# power_cpu.net
KiCad netlist of a schematic drawn in Altium Designer
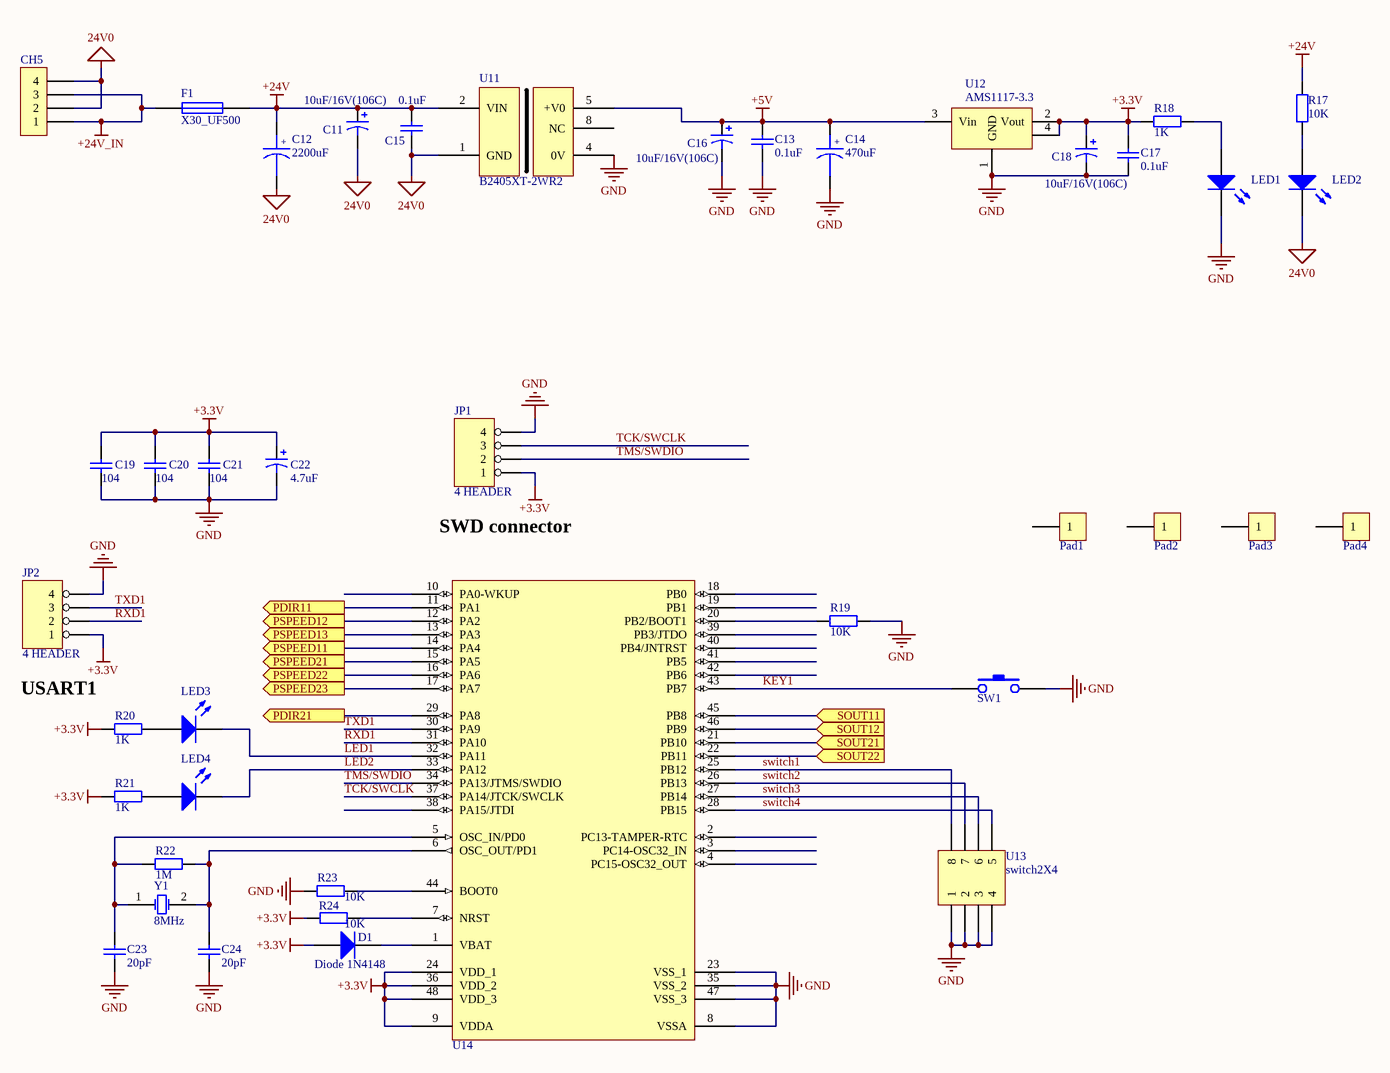
[diagram p0: power_cpu.SchDoc]

(export (version "E")
  (design (tool "Eeschema 10.0.6"))
  (components
    (comp (ref "C11")
      (value "10uF/16V(106C)")
      (footprint "CAP A-3216")
      (description "Polarized Capacitor (Surface Mount)")
      (fields (field (name "Comment") "Cap Pol3") (field (name "PUBLISHER") "Altium Limited"))
      (libsource (lib "Miscellaneous Devices") (part "Cap Pol3"))
    )
    (comp (ref "C12")
      (value "C_2200uF")
      (footprint "C7.8*17")
      (fields (field (name "ALTIUM_UNNAMED_1") "2200uF"))
      (libsource (lib "myIntegrated_Library1") (part "C_2200uF"))
    )
    (comp (ref "C13")
      (value "0.1uF")
      (footprint "0805")
      (description "Capacitor")
      (fields (field (name "Comment") "Cap") (field (name "PUBLISHER") "Altium Limited"))
      (libsource (lib "Miscellaneous Devices") (part "Cap"))
    )
    (comp (ref "C14")
      (value "C_2200uF")
      (footprint "C5*10")
      (fields (field (name "ALTIUM_UNNAMED_1") "470uF"))
      (libsource (lib "myIntegrated_Library1") (part "C_2200uF"))
    )
    (comp (ref "C15")
      (value "0.1uF")
      (footprint "0805")
      (description "Capacitor")
      (fields (field (name "Comment") "Cap") (field (name "PUBLISHER") "Altium Limited"))
      (libsource (lib "Miscellaneous Devices") (part "Cap"))
    )
    (comp (ref "C16")
      (value "10uF/16V(106C)")
      (footprint "CAP A-3216")
      (description "Polarized Capacitor (Surface Mount)")
      (fields (field (name "Comment") "Cap Pol3") (field (name "PUBLISHER") "Altium Limited"))
      (libsource (lib "Miscellaneous Devices") (part "Cap Pol3"))
    )
    (comp (ref "C17")
      (value "0.1uF")
      (footprint "0805")
      (description "Capacitor")
      (fields (field (name "Comment") "Cap") (field (name "PUBLISHER") "Altium Limited"))
      (libsource (lib "Miscellaneous Devices") (part "Cap"))
    )
    (comp (ref "C18")
      (value "10uF/16V(106C)")
      (footprint "CAP A-3216")
      (description "Polarized Capacitor (Surface Mount)")
      (fields (field (name "Comment") "Cap Pol3") (field (name "PUBLISHER") "Altium Limited"))
      (libsource (lib "Miscellaneous Devices") (part "Cap Pol3"))
    )
    (comp (ref "C19")
      (value "104")
      (footprint "C0805tan")
      (description "Capacitor")
      (fields (field (name "Comment") "Cap") (field (name "PUBLISHER") "Altium Limited"))
      (libsource (lib "Miscellaneous Devices") (part "Cap"))
    )
    (comp (ref "C20")
      (value "104")
      (footprint "C0805tan")
      (description "Capacitor")
      (fields (field (name "Comment") "Cap") (field (name "PUBLISHER") "Altium Limited"))
      (libsource (lib "Miscellaneous Devices") (part "Cap"))
    )
    (comp (ref "C21")
      (value "104")
      (footprint "C0805tan")
      (description "Capacitor")
      (fields (field (name "Comment") "Cap") (field (name "PUBLISHER") "Altium Limited"))
      (libsource (lib "Miscellaneous Devices") (part "Cap"))
    )
    (comp (ref "C22")
      (value "4.7uF")
      (footprint "3225[1210]")
      (description "Polarized Capacitor (Radial)")
      (fields (field (name "Comment") "Cap Pol1") (field (name "PUBLISHER") "Altium Limited"))
      (libsource (lib "Miscellaneous Devices") (part "Cap Pol1"))
    )
    (comp (ref "C23")
      (value "20pF")
      (footprint "C0805tan")
      (description "Capacitor")
      (fields (field (name "Comment") "Cap") (field (name "PUBLISHER") "Altium Limited"))
      (libsource (lib "开发板元件库") (part "Cap"))
    )
    (comp (ref "C24")
      (value "20pF")
      (footprint "C0805tan")
      (description "Capacitor")
      (fields (field (name "Comment") "Cap") (field (name "PUBLISHER") "Altium Limited"))
      (libsource (lib "开发板元件库") (part "Cap"))
    )
    (comp (ref "CH5")
      (value "HEADER1X4")
      (footprint "CH3.96-4PIN")
      (libsource (lib "myIntegrated_Library1") (part "HEADER1X4"))
    )
    (comp (ref "D1")
      (value "Diode 1N4148")
      (footprint "LL34")
      (description "High Conductance Fast Diode")
      (fields (field (name "PUBLISHER") "Altium Limited"))
      (libsource (lib "Miscellaneous Devices") (part "Diode 1N4148"))
    )
    (comp (ref "F1")
      (value "X30_UF500")
      (footprint "X30UF600")
      (description "Fuse")
      (fields (field (name "PUBLISHER") "Altium Limited"))
      (libsource (lib "Miscellaneous Devices") (part "Fuse 1"))
    )
    (comp (ref "JP1")
      (value "4 HEADER")
      (footprint "CON4_1.5")
      (description "4 Pin Header")
      (libsource (lib "Miscellaneous Devices") (part "4 HEADER"))
    )
    (comp (ref "JP2")
      (value "4 HEADER")
      (footprint "HDR1X4")
      (description "4 Pin Header")
      (libsource (lib "Miscellaneous Devices") (part "4 HEADER"))
    )
    (comp (ref "LED1")
      (value "~")
      (footprint "LED-0805")
      (description "Typical RED, GREEN, YELLOW, AMBER GaAs LED")
      (fields (field (name "PUBLISHER") "Altium Limited"))
      (libsource (lib "Miscellaneous Devices") (part "LED2"))
    )
    (comp (ref "LED2")
      (value "~")
      (footprint "LED-0805")
      (description "Typical RED, GREEN, YELLOW, AMBER GaAs LED")
      (fields (field (name "PUBLISHER") "Altium Limited"))
      (libsource (lib "Miscellaneous Devices") (part "LED2"))
    )
    (comp (ref "LED3")
      (value "~")
      (footprint "LED-0805")
      (description "Typical RED, GREEN, YELLOW, AMBER GaAs LED")
      (fields (field (name "PUBLISHER") "Altium Limited"))
      (libsource (lib "Miscellaneous Devices") (part "LED2"))
    )
    (comp (ref "LED4")
      (value "~")
      (footprint "LED-0805")
      (description "Typical RED, GREEN, YELLOW, AMBER GaAs LED")
      (fields (field (name "PUBLISHER") "Altium Limited"))
      (libsource (lib "Miscellaneous Devices") (part "LED2"))
    )
    (comp (ref "Pad1")
      (value "Pad")
      (footprint "pad35")
      (libsource (lib "myIntegrated_Library1") (part "Pad"))
    )
    (comp (ref "Pad2")
      (value "Pad")
      (footprint "pad35")
      (libsource (lib "myIntegrated_Library1") (part "Pad"))
    )
    (comp (ref "Pad3")
      (value "Pad")
      (footprint "pad35")
      (libsource (lib "myIntegrated_Library1") (part "Pad"))
    )
    (comp (ref "Pad4")
      (value "Pad")
      (footprint "pad35")
      (libsource (lib "myIntegrated_Library1") (part "Pad"))
    )
    (comp (ref "R17")
      (value "10K")
      (footprint "0805")
      (description "Resistor")
      (fields (field (name "Comment") "Res2") (field (name "PUBLISHER") "Altium Limited"))
      (libsource (lib "") (part "Res2_1"))
    )
    (comp (ref "R18")
      (value "1K")
      (footprint "0805")
      (description "Resistor")
      (fields (field (name "Comment") "Res2") (field (name "PUBLISHER") "Altium Limited"))
      (libsource (lib "Miscellaneous Devices") (part "Res2"))
    )
    (comp (ref "R19")
      (value "10K")
      (footprint "C0805tan")
      (description "Resistor")
      (fields (field (name "Comment") "Res2") (field (name "PUBLISHER") "Altium Limited"))
      (libsource (lib "开发板元件库") (part "Res2"))
    )
    (comp (ref "R20")
      (value "1K")
      (footprint "0805")
      (description "Resistor")
      (fields (field (name "Comment") "Res2") (field (name "PUBLISHER") "Altium Limited"))
      (libsource (lib "Miscellaneous Devices") (part "Res2"))
    )
    (comp (ref "R21")
      (value "1K")
      (footprint "0805")
      (description "Resistor")
      (fields (field (name "Comment") "Res2") (field (name "PUBLISHER") "Altium Limited"))
      (libsource (lib "Miscellaneous Devices") (part "Res2"))
    )
    (comp (ref "R22")
      (value "1M")
      (footprint "C0805tan")
      (description "Resistor")
      (fields (field (name "Comment") "Res2") (field (name "PUBLISHER") "Altium Limited"))
      (libsource (lib "开发板元件库") (part "Res2"))
    )
    (comp (ref "R23")
      (value "10K")
      (footprint "C0805tan")
      (description "Resistor")
      (fields (field (name "Comment") "Res2") (field (name "PUBLISHER") "Altium Limited"))
      (libsource (lib "开发板元件库") (part "Res2"))
    )
    (comp (ref "R24")
      (value "10K")
      (footprint "C0805tan")
      (description "Resistor")
      (fields (field (name "Comment") "Res2") (field (name "PUBLISHER") "Altium Limited"))
      (libsource (lib "开发板元件库") (part "Res2"))
    )
    (comp (ref "SW1")
      (value "SW-KEY-2")
      (footprint "KEY_SOP4")
      (libsource (lib "myIntegrated_Library1") (part "SW-KEY-2"))
    )
    (comp (ref "U11")
      (value "B2405XT-2WR2")
      (footprint "B2405XT-2WR2")
      (libsource (lib "myIntegrated_Library1") (part "B2405XT-2WR2"))
    )
    (comp (ref "U12")
      (value "AMS1117-3.3")
      (footprint "SOT223")
      (libsource (lib "货架电子标签元件库") (part "AMS1117-5"))
    )
    (comp (ref "U13")
      (value "switch2X4")
      (footprint "SOP8_switch")
      (libsource (lib "myIntegrated_Library1") (part "switch2X4"))
    )
    (comp (ref "U14")
      (value "STM32F103C8T6")
      (footprint "LQFP48")
      (libsource (lib "myIntegrated_Library1") (part "STM32F103C8T6"))
    )
    (comp (ref "Y1")
      (value "8MHz")
      (footprint "XTAL_US")
      (description "Crystal Oscillator")
      (fields (field (name "PUBLISHER") "Altium Limited"))
      (libsource (lib "战舰STM32开发板底板封装库") (part "XTAL"))
    )
  )
  (nets
    (net (code "1") (name "+3.3V") (class "Default")
      (node (ref "C17") (pin "2") (pinfunction "2_2") (pintype "passive"))
      (node (ref "C18") (pin "1") (pinfunction "1_1") (pintype "passive"))
      (node (ref "C19") (pin "2") (pinfunction "2_2") (pintype "passive"))
      (node (ref "C20") (pin "2") (pinfunction "2_2") (pintype "passive"))
      (node (ref "C21") (pin "2") (pinfunction "2_2") (pintype "passive"))
      (node (ref "C22") (pin "1") (pinfunction "1_1") (pintype "passive"))
      (node (ref "D1") (pin "1") (pinfunction "A_1") (pintype "passive"))
      (node (ref "JP1") (pin "1") (pinfunction "1_1") (pintype "passive"))
      (node (ref "JP2") (pin "1") (pinfunction "1_1") (pintype "passive"))
      (node (ref "R18") (pin "2") (pinfunction "2_2") (pintype "passive"))
      (node (ref "R20") (pin "2") (pinfunction "2_2") (pintype "passive"))
      (node (ref "R21") (pin "2") (pinfunction "2_2") (pintype "passive"))
      (node (ref "R24") (pin "1") (pinfunction "1_1") (pintype "passive"))
      (node (ref "U12") (pin "2") (pinfunction "Vout_2") (pintype "passive"))
      (node (ref "U12") (pin "4") (pintype "passive"))
      (node (ref "U14") (pin "24") (pinfunction "VDD_1_24") (pintype "power_in"))
      (node (ref "U14") (pin "36") (pinfunction "VDD_2_36") (pintype "power_in"))
      (node (ref "U14") (pin "48") (pinfunction "VDD_3_48") (pintype "power_in"))
      (node (ref "U14") (pin "9") (pinfunction "VDDA_9") (pintype "power_in"))
    )
    (net (code "2") (name "+5V") (class "Default")
      (node (ref "C13") (pin "2") (pinfunction "2_2") (pintype "passive"))
      (node (ref "C14") (pin "1") (pinfunction "1_1") (pintype "passive"))
      (node (ref "C16") (pin "1") (pinfunction "1_1") (pintype "passive"))
      (node (ref "U11") (pin "5") (pinfunction "+V0_5") (pintype "passive"))
      (node (ref "U12") (pin "3") (pinfunction "Vin_3") (pintype "passive"))
    )
    (net (code "3") (name "+24V") (class "Default")
      (node (ref "C11") (pin "1") (pinfunction "1_1") (pintype "passive"))
      (node (ref "C12") (pin "1") (pinfunction "1_1") (pintype "passive"))
      (node (ref "C15") (pin "2") (pinfunction "2_2") (pintype "passive"))
      (node (ref "F1") (pin "2") (pinfunction "2_2") (pintype "passive"))
      (node (ref "R17") (pin "2") (pinfunction "2_2") (pintype "passive"))
      (node (ref "U11") (pin "2") (pinfunction "VIN_2") (pintype "passive"))
    )
    (net (code "4") (name "+24V_IN") (class "Default")
      (node (ref "CH5") (pin "1") (pinfunction "1_1") (pintype "passive"))
      (node (ref "CH5") (pin "3") (pinfunction "3_3") (pintype "passive"))
      (node (ref "F1") (pin "1") (pinfunction "1_1") (pintype "passive"))
    )
    (net (code "5") (name "/KEY1") (class "Default")
      (node (ref "SW1") (pin "1") (pinfunction "1_1") (pintype "passive"))
      (node (ref "U14") (pin "43") (pinfunction "PB7_43") (pintype "bidirectional"))
    )
    (net (code "6") (name "/LED1") (class "Default")
      (node (ref "LED3") (pin "2") (pinfunction "K_2") (pintype "passive"))
      (node (ref "U14") (pin "32") (pinfunction "PA11_32") (pintype "bidirectional"))
    )
    (net (code "7") (name "/LED2") (class "Default")
      (node (ref "LED4") (pin "2") (pinfunction "K_2") (pintype "passive"))
      (node (ref "U14") (pin "33") (pinfunction "PA12_33") (pintype "bidirectional"))
    )
    (net (code "8") (name "/PDIR11") (class "Default")
      (node (ref "U14") (pin "11") (pinfunction "PA1_11") (pintype "bidirectional"))
    )
    (net (code "9") (name "/PDIR21") (class "Default")
      (node (ref "U14") (pin "29") (pinfunction "PA8_29") (pintype "bidirectional"))
    )
    (net (code "10") (name "/PSPEED11") (class "Default")
      (node (ref "U14") (pin "14") (pinfunction "PA4_14") (pintype "bidirectional"))
    )
    (net (code "11") (name "/PSPEED12") (class "Default")
      (node (ref "U14") (pin "12") (pinfunction "PA2_12") (pintype "bidirectional"))
    )
    (net (code "12") (name "/PSPEED13") (class "Default")
      (node (ref "U14") (pin "13") (pinfunction "PA3_13") (pintype "bidirectional"))
    )
    (net (code "13") (name "/PSPEED21") (class "Default")
      (node (ref "U14") (pin "15") (pinfunction "PA5_15") (pintype "bidirectional"))
    )
    (net (code "14") (name "/PSPEED22") (class "Default")
      (node (ref "U14") (pin "16") (pinfunction "PA6_16") (pintype "bidirectional"))
    )
    (net (code "15") (name "/PSPEED23") (class "Default")
      (node (ref "U14") (pin "17") (pinfunction "PA7_17") (pintype "bidirectional"))
    )
    (net (code "16") (name "/RXD1") (class "Default")
      (node (ref "JP2") (pin "2") (pinfunction "2_2") (pintype "passive"))
      (node (ref "U14") (pin "31") (pinfunction "PA10_31") (pintype "bidirectional"))
    )
    (net (code "17") (name "/SOUT11") (class "Default")
      (node (ref "U14") (pin "45") (pinfunction "PB8_45") (pintype "bidirectional"))
    )
    (net (code "18") (name "/SOUT12") (class "Default")
      (node (ref "U14") (pin "46") (pinfunction "PB9_46") (pintype "bidirectional"))
    )
    (net (code "19") (name "/SOUT21") (class "Default")
      (node (ref "U14") (pin "21") (pinfunction "PB10_21") (pintype "bidirectional"))
    )
    (net (code "20") (name "/SOUT22") (class "Default")
      (node (ref "U14") (pin "22") (pinfunction "PB11_22") (pintype "bidirectional"))
    )
    (net (code "21") (name "/TCK{slash}SWCLK") (class "Default")
      (node (ref "JP1") (pin "3") (pinfunction "3_3") (pintype "passive"))
      (node (ref "U14") (pin "37") (pinfunction "PA14/JTCK/SWCLK_37") (pintype "bidirectional"))
    )
    (net (code "22") (name "/TMS{slash}SWDIO") (class "Default")
      (node (ref "JP1") (pin "2") (pinfunction "2_2") (pintype "passive"))
      (node (ref "U14") (pin "34") (pinfunction "PA13/JTMS/SWDIO_34") (pintype "bidirectional"))
    )
    (net (code "23") (name "/TXD1") (class "Default")
      (node (ref "JP2") (pin "3") (pinfunction "3_3") (pintype "passive"))
      (node (ref "U14") (pin "30") (pinfunction "PA9_30") (pintype "bidirectional"))
    )
    (net (code "24") (name "/switch1") (class "Default")
      (node (ref "U13") (pin "8") (pinfunction "8_8") (pintype "passive"))
      (node (ref "U14") (pin "25") (pinfunction "PB12_25") (pintype "bidirectional"))
    )
    (net (code "25") (name "/switch2") (class "Default")
      (node (ref "U13") (pin "7") (pinfunction "7_7") (pintype "passive"))
      (node (ref "U14") (pin "26") (pinfunction "PB13_26") (pintype "bidirectional"))
    )
    (net (code "26") (name "/switch3") (class "Default")
      (node (ref "U13") (pin "6") (pinfunction "6_6") (pintype "passive"))
      (node (ref "U14") (pin "27") (pinfunction "PB14_27") (pintype "bidirectional"))
    )
    (net (code "27") (name "/switch4") (class "Default")
      (node (ref "U13") (pin "5") (pinfunction "5_5") (pintype "passive"))
      (node (ref "U14") (pin "28") (pinfunction "PB15_28") (pintype "bidirectional"))
    )
    (net (code "28") (name "24V0") (class "Default")
      (node (ref "C11") (pin "2") (pinfunction "2_2") (pintype "passive"))
      (node (ref "C12") (pin "2") (pinfunction "2_2") (pintype "passive"))
      (node (ref "C15") (pin "1") (pinfunction "1_1") (pintype "passive"))
      (node (ref "CH5") (pin "2") (pinfunction "2_2") (pintype "passive"))
      (node (ref "CH5") (pin "4") (pinfunction "4_4") (pintype "passive"))
      (node (ref "LED2") (pin "2") (pinfunction "K_2") (pintype "passive"))
      (node (ref "U11") (pin "1") (pinfunction "GND_1") (pintype "passive"))
    )
    (net (code "29") (name "GND") (class "Default")
      (node (ref "C13") (pin "1") (pinfunction "1_1") (pintype "passive"))
      (node (ref "C14") (pin "2") (pinfunction "2_2") (pintype "passive"))
      (node (ref "C16") (pin "2") (pinfunction "2_2") (pintype "passive"))
      (node (ref "C17") (pin "1") (pinfunction "1_1") (pintype "passive"))
      (node (ref "C18") (pin "2") (pinfunction "2_2") (pintype "passive"))
      (node (ref "C19") (pin "1") (pinfunction "1_1") (pintype "passive"))
      (node (ref "C20") (pin "1") (pinfunction "1_1") (pintype "passive"))
      (node (ref "C21") (pin "1") (pinfunction "1_1") (pintype "passive"))
      (node (ref "C22") (pin "2") (pinfunction "2_2") (pintype "passive"))
      (node (ref "C23") (pin "1") (pinfunction "1_1") (pintype "passive"))
      (node (ref "C24") (pin "1") (pinfunction "1_1") (pintype "passive"))
      (node (ref "JP1") (pin "4") (pinfunction "4_4") (pintype "passive"))
      (node (ref "JP2") (pin "4") (pinfunction "4_4") (pintype "passive"))
      (node (ref "LED1") (pin "2") (pinfunction "K_2") (pintype "passive"))
      (node (ref "R19") (pin "2") (pinfunction "2_2") (pintype "passive"))
      (node (ref "R23") (pin "1") (pinfunction "1_1") (pintype "passive"))
      (node (ref "SW1") (pin "2") (pinfunction "2_2") (pintype "passive"))
      (node (ref "U11") (pin "4") (pinfunction "0V_4") (pintype "passive"))
      (node (ref "U12") (pin "1") (pinfunction "GND_1") (pintype "passive"))
      (node (ref "U13") (pin "1") (pinfunction "1_1") (pintype "passive"))
      (node (ref "U13") (pin "2") (pinfunction "2_2") (pintype "passive"))
      (node (ref "U13") (pin "3") (pinfunction "3_3") (pintype "passive"))
      (node (ref "U13") (pin "4") (pinfunction "4_4") (pintype "passive"))
      (node (ref "U14") (pin "23") (pinfunction "VSS_1_23") (pintype "power_in"))
      (node (ref "U14") (pin "35") (pinfunction "VSS_2_35") (pintype "power_in"))
      (node (ref "U14") (pin "47") (pinfunction "VSS_3_47") (pintype "power_in"))
      (node (ref "U14") (pin "8") (pinfunction "VSSA_8") (pintype "power_in"))
    )
    (net (code "30") (name "Net-(D1-K)") (class "Default")
      (node (ref "D1") (pin "2") (pinfunction "K_2") (pintype "passive"))
      (node (ref "U14") (pin "1") (pinfunction "VBAT_1") (pintype "power_in"))
    )
    (net (code "31") (name "Net-(LED1-A)") (class "Default")
      (node (ref "LED1") (pin "1") (pinfunction "A_1") (pintype "passive"))
      (node (ref "R18") (pin "1") (pinfunction "1_1") (pintype "passive"))
    )
    (net (code "32") (name "Net-(LED2-A)") (class "Default")
      (node (ref "LED2") (pin "1") (pinfunction "A_1") (pintype "passive"))
      (node (ref "R17") (pin "1") (pinfunction "1_1") (pintype "passive"))
    )
    (net (code "33") (name "Net-(LED3-A)") (class "Default")
      (node (ref "LED3") (pin "1") (pinfunction "A_1") (pintype "passive"))
      (node (ref "R20") (pin "1") (pinfunction "1_1") (pintype "passive"))
    )
    (net (code "34") (name "Net-(LED4-A)") (class "Default")
      (node (ref "LED4") (pin "1") (pinfunction "A_1") (pintype "passive"))
      (node (ref "R21") (pin "1") (pinfunction "1_1") (pintype "passive"))
    )
    (net (code "35") (name "Net-(U14-BOOT0)") (class "Default")
      (node (ref "R23") (pin "2") (pinfunction "2_2") (pintype "passive"))
      (node (ref "U14") (pin "44") (pinfunction "BOOT0_44") (pintype "input"))
    )
    (net (code "36") (name "Net-(U14-NRST)") (class "Default")
      (node (ref "R24") (pin "2") (pinfunction "2_2") (pintype "passive"))
      (node (ref "U14") (pin "7") (pinfunction "NRST_7") (pintype "bidirectional"))
    )
    (net (code "37") (name "Net-(U14-OSC_IN{slash}PD0)") (class "Default")
      (node (ref "C23") (pin "2") (pinfunction "2_2") (pintype "passive"))
      (node (ref "R22") (pin "1") (pinfunction "1_1") (pintype "passive"))
      (node (ref "U14") (pin "5") (pinfunction "OSC_IN/PD0_5") (pintype "input"))
      (node (ref "Y1") (pin "1") (pinfunction "OSC1_1") (pintype "passive"))
    )
    (net (code "38") (name "Net-(U14-OSC_OUT{slash}PD1)") (class "Default")
      (node (ref "C24") (pin "2") (pinfunction "2_2") (pintype "passive"))
      (node (ref "R22") (pin "2") (pinfunction "2_2") (pintype "passive"))
      (node (ref "U14") (pin "6") (pinfunction "OSC_OUT/PD1_6") (pintype "output"))
      (node (ref "Y1") (pin "2") (pinfunction "OSC2_2") (pintype "passive"))
    )
    (net (code "39") (name "Net-(U14-PB2{slash}BOOT1)") (class "Default")
      (node (ref "R19") (pin "1") (pinfunction "1_1") (pintype "passive"))
      (node (ref "U14") (pin "20") (pinfunction "PB2/BOOT1_20") (pintype "bidirectional"))
    )
    (net (code "40") (name "unconnected-(Pad1-Pad1)") (class "Default")
      (node (ref "Pad1") (pin "1") (pinfunction "1_1") (pintype "passive"))
    )
    (net (code "41") (name "unconnected-(Pad2-Pad1)") (class "Default")
      (node (ref "Pad2") (pin "1") (pinfunction "1_1") (pintype "passive"))
    )
    (net (code "42") (name "unconnected-(Pad3-Pad1)") (class "Default")
      (node (ref "Pad3") (pin "1") (pinfunction "1_1") (pintype "passive"))
    )
    (net (code "43") (name "unconnected-(Pad4-Pad1)") (class "Default")
      (node (ref "Pad4") (pin "1") (pinfunction "1_1") (pintype "passive"))
    )
    (net (code "44") (name "unconnected-(U11-NC-Pad8)") (class "Default")
      (node (ref "U11") (pin "8") (pinfunction "NC_8") (pintype "passive"))
    )
    (net (code "45") (name "unconnected-(U14-PA0-WKUP-Pad10)") (class "Default")
      (node (ref "U14") (pin "10") (pinfunction "PA0-WKUP_10") (pintype "bidirectional"))
    )
    (net (code "46") (name "unconnected-(U14-PA15{slash}JTDI-Pad38)") (class "Default")
      (node (ref "U14") (pin "38") (pinfunction "PA15/JTDI_38") (pintype "bidirectional"))
    )
    (net (code "47") (name "unconnected-(U14-PB0-Pad18)") (class "Default")
      (node (ref "U14") (pin "18") (pinfunction "PB0_18") (pintype "bidirectional"))
    )
    (net (code "48") (name "unconnected-(U14-PB1-Pad19)") (class "Default")
      (node (ref "U14") (pin "19") (pinfunction "PB1_19") (pintype "bidirectional"))
    )
    (net (code "49") (name "unconnected-(U14-PB3{slash}JTDO-Pad39)") (class "Default")
      (node (ref "U14") (pin "39") (pinfunction "PB3/JTDO_39") (pintype "bidirectional"))
    )
    (net (code "50") (name "unconnected-(U14-PB4{slash}JNTRST-Pad40)") (class "Default")
      (node (ref "U14") (pin "40") (pinfunction "PB4/JNTRST_40") (pintype "bidirectional"))
    )
    (net (code "51") (name "unconnected-(U14-PB5-Pad41)") (class "Default")
      (node (ref "U14") (pin "41") (pinfunction "PB5_41") (pintype "bidirectional"))
    )
    (net (code "52") (name "unconnected-(U14-PB6-Pad42)") (class "Default")
      (node (ref "U14") (pin "42") (pinfunction "PB6_42") (pintype "bidirectional"))
    )
    (net (code "53") (name "unconnected-(U14-PC13-TAMPER-RTC-Pad2)") (class "Default")
      (node (ref "U14") (pin "2") (pinfunction "PC13-TAMPER-RTC_2") (pintype "bidirectional"))
    )
    (net (code "54") (name "unconnected-(U14-PC14-OSC32_IN-Pad3)") (class "Default")
      (node (ref "U14") (pin "3") (pinfunction "PC14-OSC32_IN_3") (pintype "bidirectional"))
    )
    (net (code "55") (name "unconnected-(U14-PC15-OSC32_OUT-Pad4)") (class "Default")
      (node (ref "U14") (pin "4") (pinfunction "PC15-OSC32_OUT_4") (pintype "bidirectional"))
    )
  )
)
